# batt_test.net
KiCad netlist of a schematic drawn in EAGLE
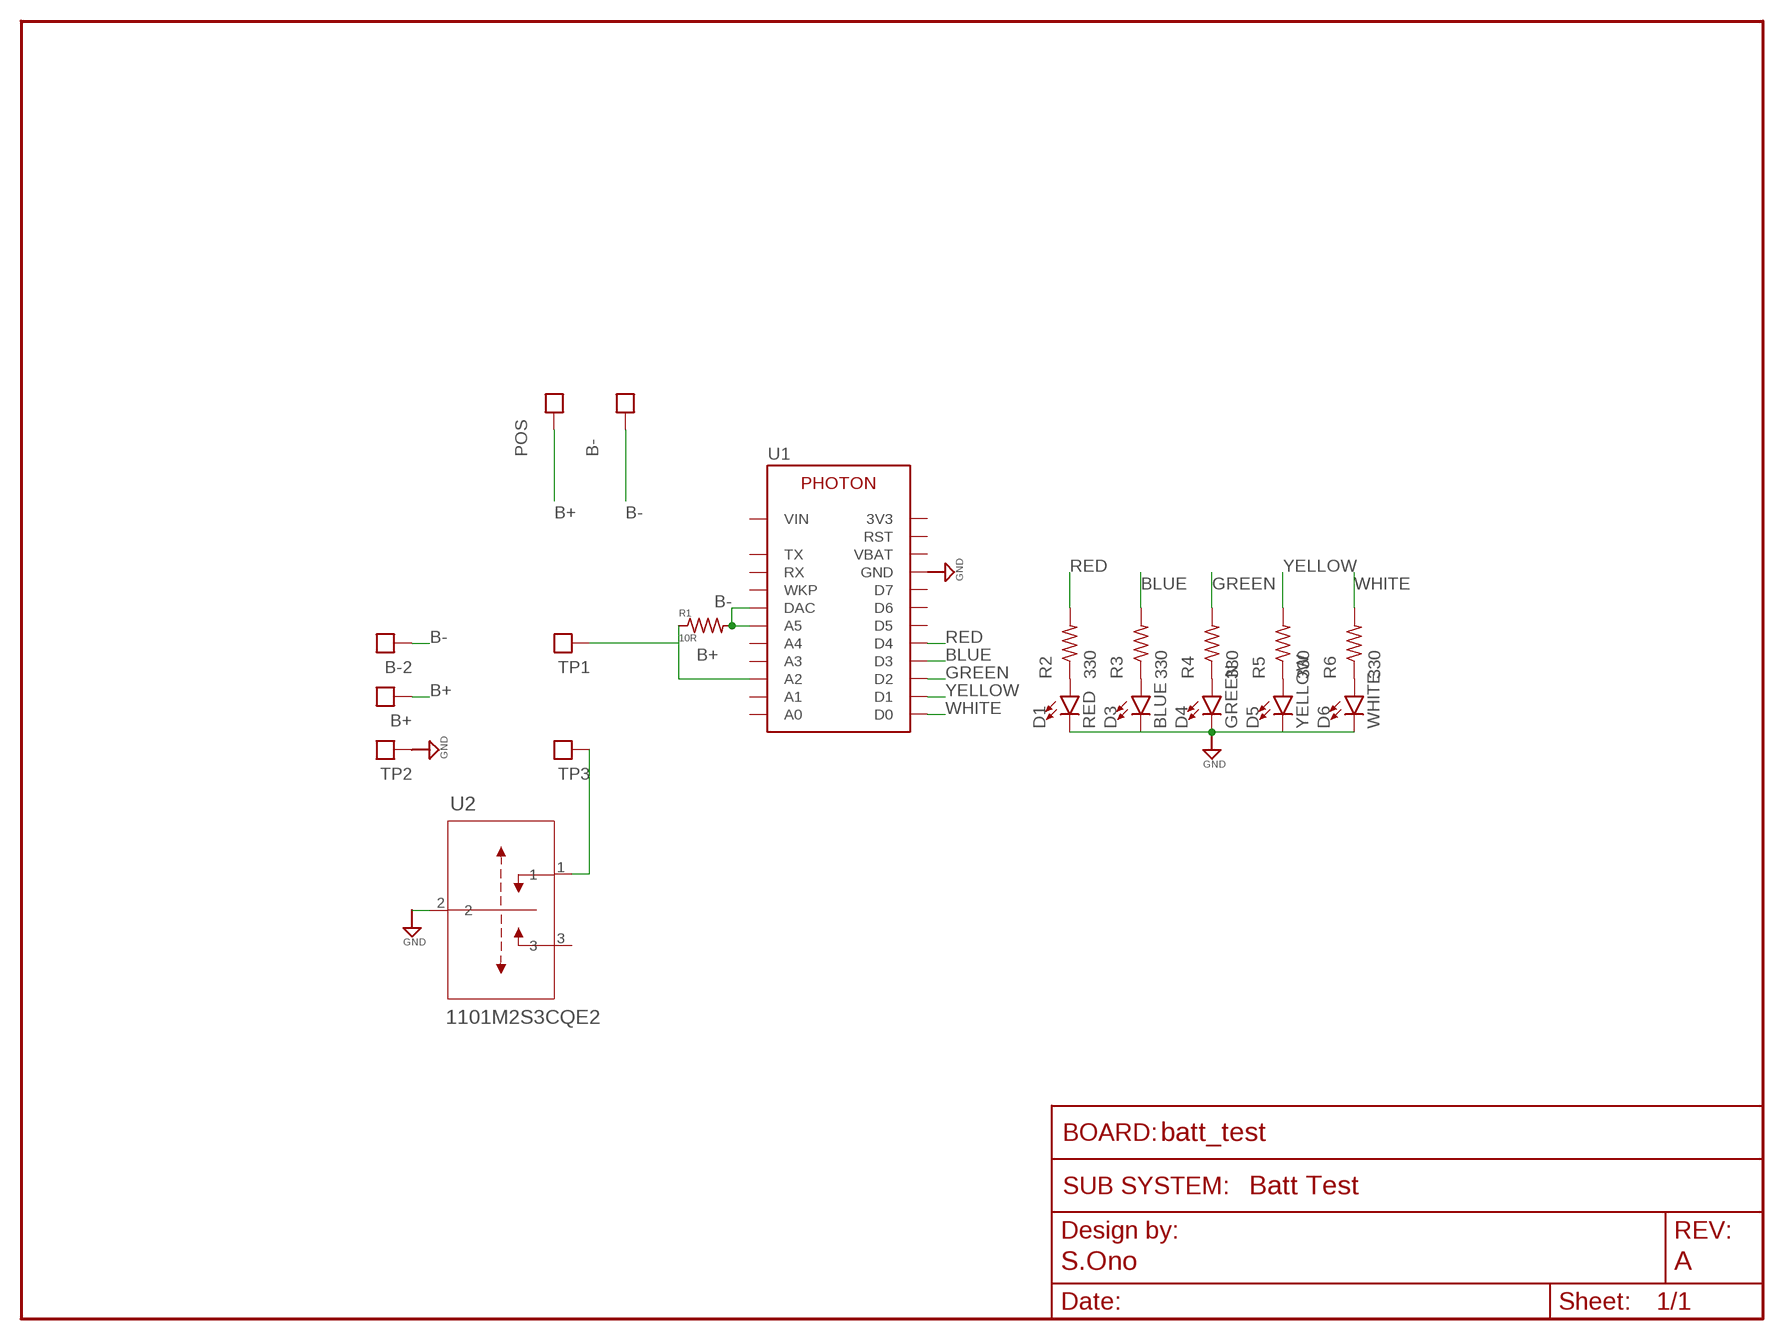
[diagram p0: schematic, sheet 1]

(export (version "E")
  (design (tool "Eeschema 10.0.6"))
  (components
    (comp (ref "B+")
      (value "TEST_POINTTHRU")
      (footprint "eagle-import:TEST_POINT")
      (libsource (lib "eagle-import") (part "TEST_POINTTHRU"))
    )
    (comp (ref "B-")
      (value "TEST_POINT")
      (footprint "eagle-import:TEST_POINT-1206")
      (libsource (lib "eagle-import") (part "TEST_POINT"))
    )
    (comp (ref "B-2")
      (value "TEST_POINTTHRU")
      (footprint "eagle-import:TEST_POINT")
      (libsource (lib "eagle-import") (part "TEST_POINTTHRU"))
    )
    (comp (ref "D1")
      (value "RED")
      (footprint "eagle-import:LED-0603")
      (libsource (lib "eagle-import") (part "LED0603"))
    )
    (comp (ref "D3")
      (value "BLUE")
      (footprint "eagle-import:LED-0603")
      (libsource (lib "eagle-import") (part "LED0603"))
    )
    (comp (ref "D4")
      (value "GREEN")
      (footprint "eagle-import:LED-0603")
      (libsource (lib "eagle-import") (part "LED0603"))
    )
    (comp (ref "D5")
      (value "YELLOW")
      (footprint "eagle-import:LED-0603")
      (libsource (lib "eagle-import") (part "LED0603"))
    )
    (comp (ref "D6")
      (value "WHITE")
      (footprint "eagle-import:LED-0603")
      (libsource (lib "eagle-import") (part "LED0603"))
    )
    (comp (ref "POS")
      (value "TEST_POINT")
      (footprint "eagle-import:TEST_POINT-1206")
      (libsource (lib "eagle-import") (part "TEST_POINT"))
    )
    (comp (ref "R1")
      (value "10R")
      (footprint "eagle-import:R0805")
      (libsource (lib "eagle-import") (part "scono_R-US_R0805"))
    )
    (comp (ref "R2")
      (value "330")
      (footprint "eagle-import:R0402")
      (libsource (lib "eagle-import") (part "R-US_R0402"))
    )
    (comp (ref "R3")
      (value "330")
      (footprint "eagle-import:R0402")
      (libsource (lib "eagle-import") (part "R-US_R0402"))
    )
    (comp (ref "R4")
      (value "330")
      (footprint "eagle-import:R0402")
      (libsource (lib "eagle-import") (part "R-US_R0402"))
    )
    (comp (ref "R5")
      (value "330")
      (footprint "eagle-import:R0402")
      (libsource (lib "eagle-import") (part "R-US_R0402"))
    )
    (comp (ref "R6")
      (value "330")
      (footprint "eagle-import:R0402")
      (libsource (lib "eagle-import") (part "R-US_R0402"))
    )
    (comp (ref "TP1")
      (value "TEST_POINTTHRU")
      (footprint "eagle-import:TEST_POINT")
      (libsource (lib "eagle-import") (part "TEST_POINTTHRU"))
    )
    (comp (ref "TP2")
      (value "TEST_POINTTHRU")
      (footprint "eagle-import:TEST_POINT")
      (libsource (lib "eagle-import") (part "TEST_POINTTHRU"))
    )
    (comp (ref "TP3")
      (value "TEST_POINTTHRU")
      (footprint "eagle-import:TEST_POINT")
      (libsource (lib "eagle-import") (part "TEST_POINTTHRU"))
    )
    (comp (ref "U1")
      (value "PHOTON")
      (footprint "eagle-import:PHOTON")
      (libsource (lib "eagle-import") (part "PHOTON"))
    )
    (comp (ref "U2")
      (value "1101M2S3CQE2")
      (footprint "eagle-import:1101M2S3CQE2")
      (libsource (lib "eagle-import") (part "1101M2S3CQE2"))
    )
  )
  (nets
    (net (code "1") (name "/B+") (class "Default")
      (node (ref "B+") (pin "1") (pinfunction "P$1_1") (pintype "bidirectional"))
      (node (ref "POS") (pin "1") (pinfunction "P$1_1") (pintype "bidirectional"))
      (node (ref "R1") (pin "1") (pinfunction "1_1") (pintype "passive"))
      (node (ref "TP1") (pin "1") (pinfunction "P$1_1") (pintype "bidirectional"))
      (node (ref "U1") (pin "A2") (pinfunction "A2_A2") (pintype "bidirectional"))
    )
    (net (code "2") (name "/B-") (class "Default")
      (node (ref "B-") (pin "1") (pinfunction "P$1_1") (pintype "bidirectional"))
      (node (ref "B-2") (pin "1") (pinfunction "P$1_1") (pintype "bidirectional"))
      (node (ref "R1") (pin "2") (pinfunction "2_2") (pintype "passive"))
      (node (ref "U1") (pin "A5") (pinfunction "A5_A5") (pintype "bidirectional"))
      (node (ref "U1") (pin "DAC") (pinfunction "DAC_DAC") (pintype "bidirectional"))
    )
    (net (code "3") (name "/BLUE") (class "Default")
      (node (ref "R3") (pin "2") (pinfunction "2_2") (pintype "passive"))
      (node (ref "U1") (pin "D3") (pinfunction "D3_D3") (pintype "bidirectional"))
    )
    (net (code "4") (name "/GREEN") (class "Default")
      (node (ref "R4") (pin "2") (pinfunction "2_2") (pintype "passive"))
      (node (ref "U1") (pin "D2") (pinfunction "D2_D2") (pintype "bidirectional"))
    )
    (net (code "5") (name "/RED") (class "Default")
      (node (ref "R2") (pin "2") (pinfunction "2_2") (pintype "passive"))
      (node (ref "U1") (pin "D4") (pinfunction "D4_D4") (pintype "bidirectional"))
    )
    (net (code "6") (name "/WHITE") (class "Default")
      (node (ref "R6") (pin "2") (pinfunction "2_2") (pintype "passive"))
      (node (ref "U1") (pin "D0") (pinfunction "D0_D0") (pintype "bidirectional"))
    )
    (net (code "7") (name "/YELLOW") (class "Default")
      (node (ref "R5") (pin "2") (pinfunction "2_2") (pintype "passive"))
      (node (ref "U1") (pin "D1") (pinfunction "D1_D1") (pintype "bidirectional"))
    )
    (net (code "8") (name "GND") (class "Default")
      (node (ref "D1") (pin "C") (pinfunction "C_C") (pintype "passive"))
      (node (ref "D3") (pin "C") (pinfunction "C_C") (pintype "passive"))
      (node (ref "D4") (pin "C") (pinfunction "C_C") (pintype "passive"))
      (node (ref "D5") (pin "C") (pinfunction "C_C") (pintype "passive"))
      (node (ref "D6") (pin "C") (pinfunction "C_C") (pintype "passive"))
      (node (ref "TP2") (pin "1") (pinfunction "P$1_1") (pintype "bidirectional"))
      (node (ref "U1") (pin "GND") (pinfunction "GND_GND") (pintype "bidirectional"))
      (node (ref "U1") (pin "GND@1") (pinfunction "GND_GND@1") (pintype "bidirectional"))
      (node (ref "U2") (pin "2") (pinfunction "2_2") (pintype "bidirectional"))
    )
    (net (code "9") (name "Net-(D1-PadA)") (class "Default")
      (node (ref "D1") (pin "A") (pinfunction "A_A") (pintype "passive"))
      (node (ref "R2") (pin "1") (pinfunction "1_1") (pintype "passive"))
    )
    (net (code "10") (name "Net-(D3-PadA)") (class "Default")
      (node (ref "D3") (pin "A") (pinfunction "A_A") (pintype "passive"))
      (node (ref "R3") (pin "1") (pinfunction "1_1") (pintype "passive"))
    )
    (net (code "11") (name "Net-(D4-PadA)") (class "Default")
      (node (ref "D4") (pin "A") (pinfunction "A_A") (pintype "passive"))
      (node (ref "R4") (pin "1") (pinfunction "1_1") (pintype "passive"))
    )
    (net (code "12") (name "Net-(D5-PadA)") (class "Default")
      (node (ref "D5") (pin "A") (pinfunction "A_A") (pintype "passive"))
      (node (ref "R5") (pin "1") (pinfunction "1_1") (pintype "passive"))
    )
    (net (code "13") (name "Net-(D6-PadA)") (class "Default")
      (node (ref "D6") (pin "A") (pinfunction "A_A") (pintype "passive"))
      (node (ref "R6") (pin "1") (pinfunction "1_1") (pintype "passive"))
    )
    (net (code "14") (name "Net-(TP3-P$1)") (class "Default")
      (node (ref "TP3") (pin "1") (pinfunction "P$1_1") (pintype "bidirectional"))
      (node (ref "U2") (pin "1") (pinfunction "1_1") (pintype "bidirectional"))
    )
    (net (code "15") (name "unconnected-(U1-Pad3V3)") (class "Default")
      (node (ref "U1") (pin "3V3") (pinfunction "3V3_3V3") (pintype "bidirectional"))
    )
    (net (code "16") (name "unconnected-(U1-PadA0)") (class "Default")
      (node (ref "U1") (pin "A0") (pinfunction "A0_A0") (pintype "bidirectional"))
    )
    (net (code "17") (name "unconnected-(U1-PadA1)") (class "Default")
      (node (ref "U1") (pin "A1") (pinfunction "A1_A1") (pintype "bidirectional"))
    )
    (net (code "18") (name "unconnected-(U1-PadA3)") (class "Default")
      (node (ref "U1") (pin "A3") (pinfunction "A3_A3") (pintype "bidirectional"))
    )
    (net (code "19") (name "unconnected-(U1-PadA4)") (class "Default")
      (node (ref "U1") (pin "A4") (pinfunction "A4_A4") (pintype "bidirectional"))
    )
    (net (code "20") (name "unconnected-(U1-PadD5)") (class "Default")
      (node (ref "U1") (pin "D5") (pinfunction "D5_D5") (pintype "bidirectional"))
    )
    (net (code "21") (name "unconnected-(U1-PadD6)") (class "Default")
      (node (ref "U1") (pin "D6") (pinfunction "D6_D6") (pintype "bidirectional"))
    )
    (net (code "22") (name "unconnected-(U1-PadD7)") (class "Default")
      (node (ref "U1") (pin "D7") (pinfunction "D7_D7") (pintype "bidirectional"))
    )
    (net (code "23") (name "unconnected-(U1-PadRST)") (class "Default")
      (node (ref "U1") (pin "RST") (pinfunction "RST_RST") (pintype "bidirectional"))
    )
    (net (code "24") (name "unconnected-(U1-PadRX)") (class "Default")
      (node (ref "U1") (pin "RX") (pinfunction "RX_RX") (pintype "bidirectional"))
    )
    (net (code "25") (name "unconnected-(U1-PadTX)") (class "Default")
      (node (ref "U1") (pin "TX") (pinfunction "TX_TX") (pintype "bidirectional"))
    )
    (net (code "26") (name "unconnected-(U1-PadVBAT)") (class "Default")
      (node (ref "U1") (pin "VBAT") (pinfunction "VBAT_VBAT") (pintype "bidirectional"))
    )
    (net (code "27") (name "unconnected-(U1-PadVIN)") (class "Default")
      (node (ref "U1") (pin "VIN") (pinfunction "VIN_VIN") (pintype "bidirectional"))
    )
    (net (code "28") (name "unconnected-(U1-PadWKP)") (class "Default")
      (node (ref "U1") (pin "WKP") (pinfunction "WKP_WKP") (pintype "bidirectional"))
    )
    (net (code "29") (name "unconnected-(U2-Pad3)") (class "Default")
      (node (ref "U2") (pin "3") (pinfunction "3_3") (pintype "bidirectional"))
    )
  )
)
